# MCU.net
KiCad netlist of a schematic drawn in Altium Designer
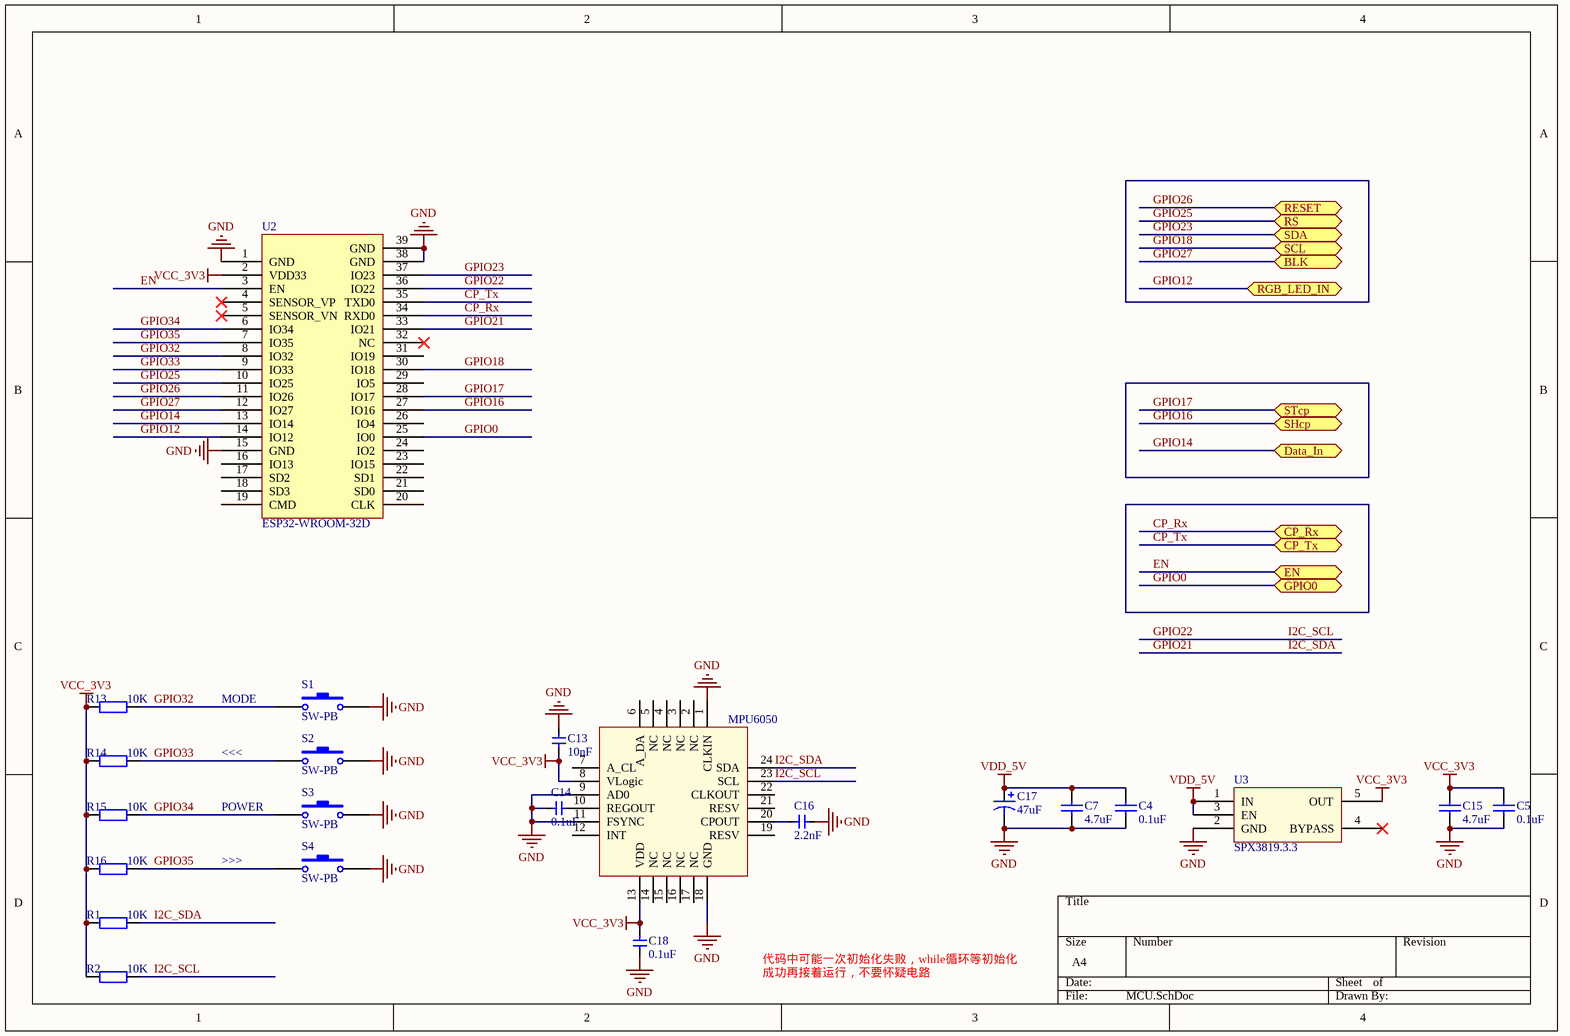
[diagram p0: MCU.SchDoc]

(export (version "E")
  (design (tool "Eeschema 10.0.6"))
  (components
    (comp (ref "C4")
      (value "0.1uF")
      (footprint "C0603")
      (description "Capacitor")
      (fields (field (name "PUBLISHER") "Altium Limited"))
      (libsource (lib "basic") (part "Cap"))
    )
    (comp (ref "C5")
      (value "0.1uF")
      (footprint "C0603")
      (description "Capacitor")
      (fields (field (name "PUBLISHER") "Altium Limited"))
      (libsource (lib "basic") (part "Cap"))
    )
    (comp (ref "C7")
      (value "4.7uF")
      (footprint "C0603")
      (description "Capacitor")
      (fields (field (name "PUBLISHER") "Altium Limited"))
      (libsource (lib "basic") (part "Cap"))
    )
    (comp (ref "C13")
      (value "10nF")
      (footprint "C0603")
      (description "Capacitor")
      (libsource (lib "MyPcbLib") (part "电容-0402"))
    )
    (comp (ref "C14")
      (value "0.1uF")
      (footprint "C0603")
      (description "Capacitor")
      (libsource (lib "MyPcbLib") (part "电容-0402"))
    )
    (comp (ref "C15")
      (value "4.7uF")
      (footprint "C0603")
      (description "Capacitor")
      (fields (field (name "PUBLISHER") "Altium Limited"))
      (libsource (lib "basic") (part "Cap"))
    )
    (comp (ref "C16")
      (value "2.2nF")
      (footprint "C0603")
      (description "Capacitor")
      (libsource (lib "MyPcbLib") (part "电容-0402"))
    )
    (comp (ref "C17")
      (value "47uF")
      (footprint "6032-C/P")
      (description "Polarized Capacitor (Radial)")
      (fields (field (name "PUBLISHER") "Altium Limited"))
      (libsource (lib "Miscellaneous Devices") (part "Cap Pol1"))
    )
    (comp (ref "C18")
      (value "0.1uF")
      (footprint "C0603")
      (description "Capacitor")
      (libsource (lib "MyPcbLib") (part "电容-0402"))
    )
    (comp (ref "R1")
      (value "10K")
      (footprint "R0603")
      (description "电阻")
      (fields (field (name "PUBLISHER") "Altium Limited"))
      (libsource (lib "My_Altium_Library") (part "Res"))
    )
    (comp (ref "R2")
      (value "10K")
      (footprint "R0603")
      (description "电阻")
      (fields (field (name "PUBLISHER") "Altium Limited"))
      (libsource (lib "My_Altium_Library") (part "Res"))
    )
    (comp (ref "R13")
      (value "10K")
      (footprint "R0603")
      (description "电阻")
      (fields (field (name "PUBLISHER") "Altium Limited"))
      (libsource (lib "My_Altium_Library") (part "Res"))
    )
    (comp (ref "R14")
      (value "10K")
      (footprint "R0603")
      (description "电阻")
      (fields (field (name "PUBLISHER") "Altium Limited"))
      (libsource (lib "My_Altium_Library") (part "Res"))
    )
    (comp (ref "R15")
      (value "10K")
      (footprint "R0603")
      (description "电阻")
      (fields (field (name "PUBLISHER") "Altium Limited"))
      (libsource (lib "My_Altium_Library") (part "Res"))
    )
    (comp (ref "R16")
      (value "10K")
      (footprint "R0603")
      (description "电阻")
      (fields (field (name "PUBLISHER") "Altium Limited"))
      (libsource (lib "My_Altium_Library") (part "Res"))
    )
    (comp (ref "S1")
      (value "SW-PB")
      (footprint "6*6*6")
      (description "Switch")
      (fields (field (name "PUBLISHER") "Altium Limited"))
      (libsource (lib "Miscellaneous Devices") (part "SW-PB"))
    )
    (comp (ref "S2")
      (value "SW-PB")
      (footprint "6*6*6")
      (description "Switch")
      (fields (field (name "PUBLISHER") "Altium Limited"))
      (libsource (lib "Miscellaneous Devices") (part "SW-PB"))
    )
    (comp (ref "S3")
      (value "SW-PB")
      (footprint "6*6*6")
      (description "Switch")
      (fields (field (name "PUBLISHER") "Altium Limited"))
      (libsource (lib "Miscellaneous Devices") (part "SW-PB"))
    )
    (comp (ref "S4")
      (value "SW-PB")
      (footprint "6*6*6")
      (description "Switch")
      (fields (field (name "PUBLISHER") "Altium Limited"))
      (libsource (lib "Miscellaneous Devices") (part "SW-PB"))
    )
    (comp (ref "U2")
      (value "ESP32-WROOM-32D")
      (footprint "ESP32-WROOM-32D")
      (libsource (lib "20211009_EleksTube_IPS_V1.2") (part "ESP32-WROOM-32D"))
    )
    (comp (ref "U3")
      (value "SPX3819.3.3")
      (footprint "SOT23-5")
      (description "LDO")
      (libsource (lib "IOC_MainBoard") (part "SPX3819.3.3"))
    )
    (comp (ref "U6")
      (value "MPU6050")
      (footprint "QFN-24")
      (description "六轴传感器")
      (libsource (lib "mLib") (part "MPU6050"))
    )
  )
  (nets
    (net (code "1") (name "/CP_Rx") (class "Default")
      (node (ref "U2") (pin "34") (pinfunction "RXD0_34") (pintype "passive"))
    )
    (net (code "2") (name "/CP_Tx") (class "Default")
      (node (ref "U2") (pin "35") (pinfunction "TXD0_35") (pintype "passive"))
    )
    (net (code "3") (name "/EN") (class "Default")
      (node (ref "U2") (pin "3") (pinfunction "EN_3") (pintype "passive"))
    )
    (net (code "4") (name "/GPIO0") (class "Default")
      (node (ref "U2") (pin "25") (pinfunction "IO0_25") (pintype "passive"))
    )
    (net (code "5") (name "/GPIO12") (class "Default")
      (node (ref "U2") (pin "14") (pinfunction "IO12_14") (pintype "passive"))
    )
    (net (code "6") (name "/GPIO14") (class "Default")
      (node (ref "U2") (pin "13") (pinfunction "IO14_13") (pintype "passive"))
    )
    (net (code "7") (name "/GPIO16") (class "Default")
      (node (ref "U2") (pin "27") (pinfunction "IO16_27") (pintype "passive"))
    )
    (net (code "8") (name "/GPIO17") (class "Default")
      (node (ref "U2") (pin "28") (pinfunction "IO17_28") (pintype "passive"))
    )
    (net (code "9") (name "/GPIO18") (class "Default")
      (node (ref "U2") (pin "30") (pinfunction "IO18_30") (pintype "passive"))
    )
    (net (code "10") (name "/GPIO21") (class "Default")
      (node (ref "R1") (pin "2") (pinfunction "2_2") (pintype "passive"))
      (node (ref "U2") (pin "33") (pinfunction "IO21_33") (pintype "passive"))
      (node (ref "U6") (pin "24") (pinfunction "SDA_24") (pintype "passive"))
    )
    (net (code "11") (name "/GPIO22") (class "Default")
      (node (ref "R2") (pin "2") (pinfunction "2_2") (pintype "passive"))
      (node (ref "U2") (pin "36") (pinfunction "IO22_36") (pintype "passive"))
      (node (ref "U6") (pin "23") (pinfunction "SCL_23") (pintype "passive"))
    )
    (net (code "12") (name "/GPIO23") (class "Default")
      (node (ref "U2") (pin "37") (pinfunction "IO23_37") (pintype "passive"))
    )
    (net (code "13") (name "/GPIO25") (class "Default")
      (node (ref "U2") (pin "10") (pinfunction "IO25_10") (pintype "passive"))
    )
    (net (code "14") (name "/GPIO26") (class "Default")
      (node (ref "U2") (pin "11") (pinfunction "IO26_11") (pintype "passive"))
    )
    (net (code "15") (name "/GPIO27") (class "Default")
      (node (ref "U2") (pin "12") (pinfunction "IO27_12") (pintype "passive"))
    )
    (net (code "16") (name "/GPIO32") (class "Default")
      (node (ref "R13") (pin "2") (pinfunction "2_2") (pintype "passive"))
      (node (ref "S1") (pin "1") (pinfunction "1_1") (pintype "passive"))
      (node (ref "U2") (pin "8") (pinfunction "IO32_8") (pintype "passive"))
    )
    (net (code "17") (name "/GPIO33") (class "Default")
      (node (ref "R14") (pin "2") (pinfunction "2_2") (pintype "passive"))
      (node (ref "S2") (pin "1") (pinfunction "1_1") (pintype "passive"))
      (node (ref "U2") (pin "9") (pinfunction "IO33_9") (pintype "passive"))
    )
    (net (code "18") (name "/GPIO34") (class "Default")
      (node (ref "R15") (pin "2") (pinfunction "2_2") (pintype "passive"))
      (node (ref "S3") (pin "1") (pinfunction "1_1") (pintype "passive"))
      (node (ref "U2") (pin "6") (pinfunction "IO34_6") (pintype "passive"))
    )
    (net (code "19") (name "/GPIO35") (class "Default")
      (node (ref "R16") (pin "2") (pinfunction "2_2") (pintype "passive"))
      (node (ref "S4") (pin "1") (pinfunction "1_1") (pintype "passive"))
      (node (ref "U2") (pin "7") (pinfunction "IO35_7") (pintype "passive"))
    )
    (net (code "20") (name "GND") (class "Default")
      (node (ref "C13") (pin "2") (pinfunction "2_2") (pintype "passive"))
      (node (ref "C14") (pin "2") (pinfunction "2_2") (pintype "passive"))
      (node (ref "C15") (pin "2") (pinfunction "2_2") (pintype "passive"))
      (node (ref "C16") (pin "1") (pinfunction "1_1") (pintype "passive"))
      (node (ref "C17") (pin "2") (pinfunction "2_2") (pintype "passive"))
      (node (ref "C18") (pin "1") (pinfunction "1_1") (pintype "passive"))
      (node (ref "C4") (pin "2") (pinfunction "2_2") (pintype "passive"))
      (node (ref "C5") (pin "2") (pinfunction "2_2") (pintype "passive"))
      (node (ref "C7") (pin "2") (pinfunction "2_2") (pintype "passive"))
      (node (ref "S1") (pin "2") (pinfunction "2_2") (pintype "passive"))
      (node (ref "S2") (pin "2") (pinfunction "2_2") (pintype "passive"))
      (node (ref "S3") (pin "2") (pinfunction "2_2") (pintype "passive"))
      (node (ref "S4") (pin "2") (pinfunction "2_2") (pintype "passive"))
      (node (ref "U2") (pin "1") (pinfunction "GND_1") (pintype "passive"))
      (node (ref "U2") (pin "15") (pinfunction "GND_15") (pintype "passive"))
      (node (ref "U2") (pin "38") (pinfunction "GND_38") (pintype "passive"))
      (node (ref "U2") (pin "39") (pinfunction "GND_39") (pintype "passive"))
      (node (ref "U3") (pin "2") (pinfunction "GND_2") (pintype "passive"))
      (node (ref "U6") (pin "1") (pinfunction "CLKIN_1") (pintype "passive"))
      (node (ref "U6") (pin "11") (pinfunction "FSYNC_11") (pintype "passive"))
      (node (ref "U6") (pin "18") (pinfunction "GND_18") (pintype "passive"))
      (node (ref "U6") (pin "9") (pinfunction "AD0_9") (pintype "passive"))
    )
    (net (code "21") (name "Net-(U6-CPOUT)") (class "Default")
      (node (ref "C16") (pin "2") (pinfunction "2_2") (pintype "passive"))
      (node (ref "U6") (pin "20") (pinfunction "CPOUT_20") (pintype "passive"))
    )
    (net (code "22") (name "Net-(U6-REGOUT)") (class "Default")
      (node (ref "C14") (pin "1") (pinfunction "1_1") (pintype "passive"))
      (node (ref "U6") (pin "10") (pinfunction "REGOUT_10") (pintype "passive"))
    )
    (net (code "23") (name "VCC_3V3") (class "Default")
      (node (ref "C13") (pin "1") (pinfunction "1_1") (pintype "passive"))
      (node (ref "C15") (pin "1") (pinfunction "1_1") (pintype "passive"))
      (node (ref "C18") (pin "2") (pinfunction "2_2") (pintype "passive"))
      (node (ref "C5") (pin "1") (pinfunction "1_1") (pintype "passive"))
      (node (ref "R1") (pin "1") (pinfunction "1_1") (pintype "passive"))
      (node (ref "R13") (pin "1") (pinfunction "1_1") (pintype "passive"))
      (node (ref "R14") (pin "1") (pinfunction "1_1") (pintype "passive"))
      (node (ref "R15") (pin "1") (pinfunction "1_1") (pintype "passive"))
      (node (ref "R16") (pin "1") (pinfunction "1_1") (pintype "passive"))
      (node (ref "R2") (pin "1") (pinfunction "1_1") (pintype "passive"))
      (node (ref "U2") (pin "2") (pinfunction "VDD33_2") (pintype "passive"))
      (node (ref "U3") (pin "5") (pinfunction "OUT_5") (pintype "passive"))
      (node (ref "U6") (pin "13") (pinfunction "VDD_13") (pintype "passive"))
      (node (ref "U6") (pin "8") (pinfunction "VLogic_8") (pintype "passive"))
    )
    (net (code "24") (name "VDD_5V") (class "Default")
      (node (ref "C17") (pin "1") (pinfunction "1_1") (pintype "passive"))
      (node (ref "C4") (pin "1") (pinfunction "1_1") (pintype "passive"))
      (node (ref "C7") (pin "1") (pinfunction "1_1") (pintype "passive"))
      (node (ref "U3") (pin "1") (pinfunction "IN_1") (pintype "passive"))
      (node (ref "U3") (pin "3") (pinfunction "EN_3") (pintype "passive"))
    )
    (net (code "25") (name "unconnected-(U2-CLK-Pad20)") (class "Default")
      (node (ref "U2") (pin "20") (pinfunction "CLK_20") (pintype "passive"))
    )
    (net (code "26") (name "unconnected-(U2-CMD-Pad19)") (class "Default")
      (node (ref "U2") (pin "19") (pinfunction "CMD_19") (pintype "passive"))
    )
    (net (code "27") (name "unconnected-(U2-IO2-Pad24)") (class "Default")
      (node (ref "U2") (pin "24") (pinfunction "IO2_24") (pintype "passive"))
    )
    (net (code "28") (name "unconnected-(U2-IO4-Pad26)") (class "Default")
      (node (ref "U2") (pin "26") (pinfunction "IO4_26") (pintype "passive"))
    )
    (net (code "29") (name "unconnected-(U2-IO5-Pad29)") (class "Default")
      (node (ref "U2") (pin "29") (pinfunction "IO5_29") (pintype "passive"))
    )
    (net (code "30") (name "unconnected-(U2-IO13-Pad16)") (class "Default")
      (node (ref "U2") (pin "16") (pinfunction "IO13_16") (pintype "passive"))
    )
    (net (code "31") (name "unconnected-(U2-IO15-Pad23)") (class "Default")
      (node (ref "U2") (pin "23") (pinfunction "IO15_23") (pintype "passive"))
    )
    (net (code "32") (name "unconnected-(U2-IO19-Pad31)") (class "Default")
      (node (ref "U2") (pin "31") (pinfunction "IO19_31") (pintype "passive"))
    )
    (net (code "33") (name "unconnected-(U2-NC-Pad32)") (class "Default")
      (node (ref "U2") (pin "32") (pinfunction "NC_32") (pintype "passive+no_connect"))
    )
    (net (code "34") (name "unconnected-(U2-SD0-Pad21)") (class "Default")
      (node (ref "U2") (pin "21") (pinfunction "SD0_21") (pintype "passive"))
    )
    (net (code "35") (name "unconnected-(U2-SD1-Pad22)") (class "Default")
      (node (ref "U2") (pin "22") (pinfunction "SD1_22") (pintype "passive"))
    )
    (net (code "36") (name "unconnected-(U2-SD2-Pad17)") (class "Default")
      (node (ref "U2") (pin "17") (pinfunction "SD2_17") (pintype "passive"))
    )
    (net (code "37") (name "unconnected-(U2-SD3-Pad18)") (class "Default")
      (node (ref "U2") (pin "18") (pinfunction "SD3_18") (pintype "passive"))
    )
    (net (code "38") (name "unconnected-(U2-SENSOR_VN-Pad5)") (class "Default")
      (node (ref "U2") (pin "5") (pinfunction "SENSOR_VN_5") (pintype "passive+no_connect"))
    )
    (net (code "39") (name "unconnected-(U2-SENSOR_VP-Pad4)") (class "Default")
      (node (ref "U2") (pin "4") (pinfunction "SENSOR_VP_4") (pintype "passive+no_connect"))
    )
    (net (code "40") (name "unconnected-(U3-BYPASS-Pad4)") (class "Default")
      (node (ref "U3") (pin "4") (pinfunction "BYPASS_4") (pintype "passive+no_connect"))
    )
    (net (code "41") (name "unconnected-(U6-A_CL-Pad7)") (class "Default")
      (node (ref "U6") (pin "7") (pinfunction "A_CL_7") (pintype "passive"))
    )
    (net (code "42") (name "unconnected-(U6-A_DA-Pad6)") (class "Default")
      (node (ref "U6") (pin "6") (pinfunction "A_DA_6") (pintype "passive"))
    )
    (net (code "43") (name "unconnected-(U6-CLKOUT-Pad22)") (class "Default")
      (node (ref "U6") (pin "22") (pinfunction "CLKOUT_22") (pintype "passive"))
    )
    (net (code "44") (name "unconnected-(U6-INT-Pad12)") (class "Default")
      (node (ref "U6") (pin "12") (pinfunction "INT_12") (pintype "passive"))
    )
    (net (code "45") (name "unconnected-(U6-NC-Pad2)") (class "Default")
      (node (ref "U6") (pin "2") (pinfunction "NC_2") (pintype "passive"))
    )
    (net (code "46") (name "unconnected-(U6-NC-Pad3)") (class "Default")
      (node (ref "U6") (pin "3") (pinfunction "NC_3") (pintype "passive"))
    )
    (net (code "47") (name "unconnected-(U6-NC-Pad4)") (class "Default")
      (node (ref "U6") (pin "4") (pinfunction "NC_4") (pintype "passive"))
    )
    (net (code "48") (name "unconnected-(U6-NC-Pad5)") (class "Default")
      (node (ref "U6") (pin "5") (pinfunction "NC_5") (pintype "passive"))
    )
    (net (code "49") (name "unconnected-(U6-NC-Pad14)") (class "Default")
      (node (ref "U6") (pin "14") (pinfunction "NC_14") (pintype "passive"))
    )
    (net (code "50") (name "unconnected-(U6-NC-Pad15)") (class "Default")
      (node (ref "U6") (pin "15") (pinfunction "NC_15") (pintype "passive"))
    )
    (net (code "51") (name "unconnected-(U6-NC-Pad16)") (class "Default")
      (node (ref "U6") (pin "16") (pinfunction "NC_16") (pintype "passive"))
    )
    (net (code "52") (name "unconnected-(U6-NC-Pad17)") (class "Default")
      (node (ref "U6") (pin "17") (pinfunction "NC_17") (pintype "passive"))
    )
    (net (code "53") (name "unconnected-(U6-RESV-Pad19)") (class "Default")
      (node (ref "U6") (pin "19") (pinfunction "RESV_19") (pintype "passive"))
    )
    (net (code "54") (name "unconnected-(U6-RESV-Pad21)") (class "Default")
      (node (ref "U6") (pin "21") (pinfunction "RESV_21") (pintype "passive"))
    )
  )
)
